# JTAG-ADAPTOR.net
KiCad netlist of a schematic drawn in Altium Designer
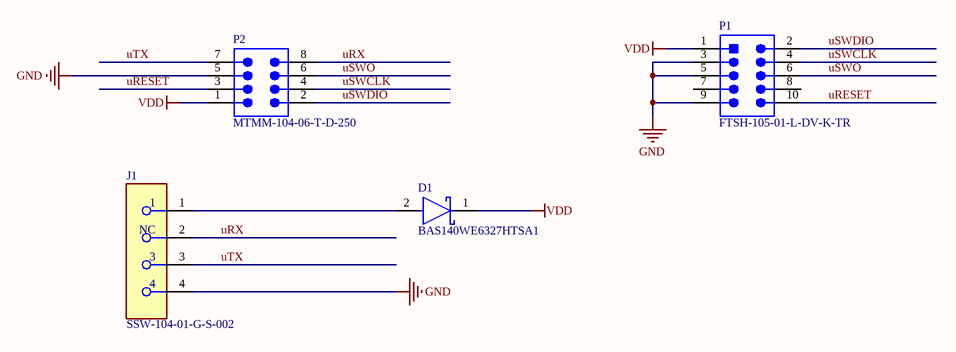
[diagram p0: JTAG-ADAPTOR.SchDoc]

(export (version "E")
  (design (tool "Eeschema 10.0.6"))
  (components
    (comp (ref "D1")
      (value "BAS140WE6327HTSA1")
      (footprint "FP-PG-SOD323-2-MFG")
      (description "DIODE SCHOTTKY 40V 120MA SOD323")
      (libsource (lib "Altium Content Vault") (part "1d6ec82d83fb6aee721767c19dac4b9"))
    )
    (comp (ref "J1")
      (value "SSW-104-01-G-S-002")
      (footprint "FP-SSW-104-01-G-S-002-MFG")
      (description "CONN RCPT 4POS 0.1 GOLD PCB")
      (fields
        (field (name "MANUFACTURER") "Samtec")
        (field (name "OCTOPART") "https://octopart.com/ssw-104-01-g-s-002-samtec-17347181")
      )
      (libsource (lib "Altium Content Vault") (part "6a27cf54b988dd932cc1b89cb2e5015"))
    )
    (comp (ref "P1")
      (value "FTSH-105-01-L-DV-K-TR")
      (footprint "SMTC-FTSH-105-01-L-DV-K_V")
      (description "Male Header, Pitch 1.27 mm, 2 x 5 Position, Height 6.12 mm, -55 to 125 degC, RoHS, Tape and Reel")
      (fields (field (name "MANUFACTURER") "SamtecInc."))
      (libsource (lib "Altium Content Vault") (part "CN-2P-M-R10"))
    )
    (comp (ref "P2")
      (value "MTMM-104-06-T-D-250")
      (footprint "SMTC-MTMM-104-06-X-D-250")
      (description "Modified Through-Hole Header, Vertical, -55 to 105 degC, 2 mm Pitch, 8-Pin, Male, RoHS")
      (fields (field (name "MANUFACTURER") "Samtec"))
      (libsource (lib "Altium Content Vault") (part "SMTC-MTMM-104-06-X-D-250"))
    )
  )
  (nets
    (net (code "1") (name "/uRESET") (class "Default")
      (node (ref "P1") (pin "10") (pinfunction "10_10") (pintype "passive"))
      (node (ref "P2") (pin "3") (pinfunction "3_3") (pintype "passive"))
    )
    (net (code "2") (name "/uRX") (class "Default")
      (node (ref "J1") (pin "2") (pinfunction "NC_2") (pintype "passive"))
      (node (ref "P2") (pin "8") (pinfunction "8_8") (pintype "passive"))
    )
    (net (code "3") (name "/uSWCLK") (class "Default")
      (node (ref "P1") (pin "4") (pinfunction "4_4") (pintype "passive"))
      (node (ref "P2") (pin "4") (pinfunction "4_4") (pintype "passive"))
    )
    (net (code "4") (name "/uSWDIO") (class "Default")
      (node (ref "P1") (pin "2") (pinfunction "2_2") (pintype "passive"))
      (node (ref "P2") (pin "2") (pinfunction "2_2") (pintype "passive"))
    )
    (net (code "5") (name "/uSWO") (class "Default")
      (node (ref "P1") (pin "6") (pinfunction "6_6") (pintype "passive"))
      (node (ref "P2") (pin "6") (pinfunction "6_6") (pintype "passive"))
    )
    (net (code "6") (name "/uTX") (class "Default")
      (node (ref "J1") (pin "3") (pinfunction "3_3") (pintype "passive"))
      (node (ref "P2") (pin "7") (pinfunction "7_7") (pintype "passive"))
    )
    (net (code "7") (name "GND") (class "Default")
      (node (ref "J1") (pin "4") (pinfunction "4_4") (pintype "passive"))
      (node (ref "P1") (pin "3") (pinfunction "3_3") (pintype "passive"))
      (node (ref "P1") (pin "5") (pinfunction "5_5") (pintype "passive"))
      (node (ref "P1") (pin "9") (pinfunction "9_9") (pintype "passive"))
      (node (ref "P2") (pin "5") (pinfunction "5_5") (pintype "passive"))
    )
    (net (code "8") (name "Net-(D1-A)") (class "Default")
      (node (ref "D1") (pin "2") (pinfunction "A_2") (pintype "passive"))
      (node (ref "J1") (pin "1") (pinfunction "1_1") (pintype "passive"))
    )
    (net (code "9") (name "VDD") (class "Default")
      (node (ref "D1") (pin "1") (pinfunction "C_1") (pintype "passive"))
      (node (ref "P1") (pin "1") (pinfunction "1_1") (pintype "passive"))
      (node (ref "P2") (pin "1") (pinfunction "1_1") (pintype "passive"))
    )
    (net (code "10") (name "unconnected-(P1-Pad7)") (class "Default")
      (node (ref "P1") (pin "7") (pinfunction "7_7") (pintype "passive"))
    )
    (net (code "11") (name "unconnected-(P1-Pad8)") (class "Default")
      (node (ref "P1") (pin "8") (pinfunction "8_8") (pintype "passive"))
    )
  )
)
